# SwitchCombo.net
KiCad netlist of a schematic drawn in EAGLE
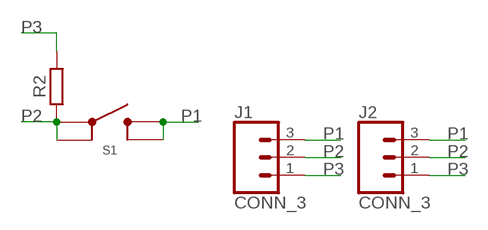
[diagram p0: schematic, sheet 1]

(export (version "E")
  (design (tool "Eeschema 10.0.6"))
  (components
    (comp (ref "J1")
      (value "CONN_3")
      (footprint "eagle-import:1X03")
      (libsource (lib "eagle-import") (part "CONN_3"))
    )
    (comp (ref "J2")
      (value "CONN_3")
      (footprint "eagle-import:1X03")
      (libsource (lib "eagle-import") (part "CONN_3"))
    )
    (comp (ref "R2")
      (value "10k")
      (footprint "eagle-import:R_TH_0.4_")
      (libsource (lib "eagle-import") (part "R-EU_TH_0.4{dblquote}"))
    )
    (comp (ref "S1")
      (value "BUTTON6X6_TH")
      (footprint "eagle-import:SWITCH_6MM_TH")
      (fields (field (name "MF") "TE Connectivity") (field (name "MPN") "1825910-6"))
      (libsource (lib "eagle-import") (part "BUTTON6X6_TH"))
    )
  )
  (nets
    (net (code "1") (name "/P1") (class "Default")
      (node (ref "J1") (pin "3") (pinfunction "3_3") (pintype "passive"))
      (node (ref "J2") (pin "3") (pinfunction "3_3") (pintype "passive"))
      (node (ref "S1") (pin "3") (pinfunction "3_3") (pintype "bidirectional"))
      (node (ref "S1") (pin "4") (pinfunction "4_4") (pintype "bidirectional"))
    )
    (net (code "2") (name "/P2") (class "Default")
      (node (ref "J1") (pin "2") (pinfunction "2_2") (pintype "passive"))
      (node (ref "J2") (pin "2") (pinfunction "2_2") (pintype "passive"))
      (node (ref "R2") (pin "P$1") (pinfunction "1_P$1") (pintype "passive"))
      (node (ref "S1") (pin "1") (pinfunction "1_1") (pintype "bidirectional"))
      (node (ref "S1") (pin "2") (pinfunction "2_2") (pintype "bidirectional"))
    )
    (net (code "3") (name "/P3") (class "Default")
      (node (ref "J1") (pin "1") (pinfunction "1_1") (pintype "passive"))
      (node (ref "J2") (pin "1") (pinfunction "1_1") (pintype "passive"))
      (node (ref "R2") (pin "P$2") (pinfunction "2_P$2") (pintype "passive"))
    )
  )
)
